# ISOW7844DWE.net
KiCad netlist of a schematic drawn in Altium Designer
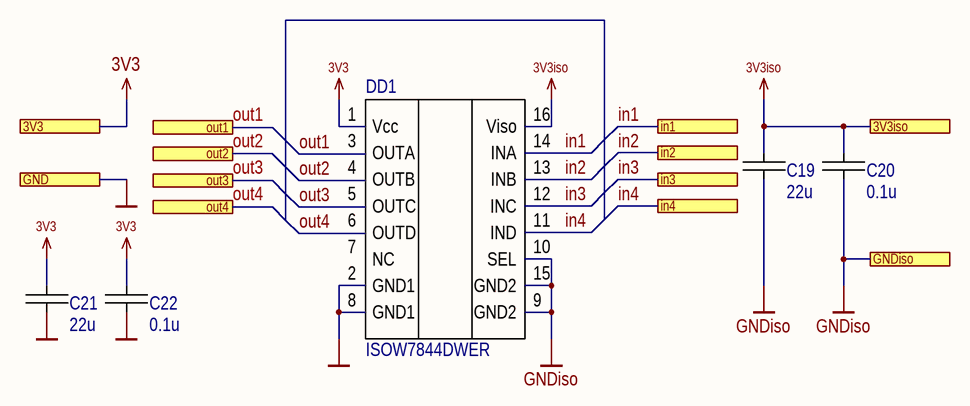
[diagram p0: ISOW7844DWE.SchDoc]

(export (version "E")
  (design (tool "Eeschema 10.0.6"))
  (components
    (comp (ref "C19")
      (value "22u")
      (footprint "C0805_IPC")
      (description "22µF ±20% 6.3V Ceramic Capacitor X5R 0805 (2012 Metric)")
      (fields (field (name "MPN") "CL21A226MQQNNNE") (field (name "TOLERANCE") "0.2"))
      (libsource (lib "DB_res_cap_ind") (part "C0805_GOST"))
    )
    (comp (ref "C20")
      (value "0.1u")
      (footprint "C0603_IPC")
      (description "0.1uF ±10% 50V Ceramic Capacitor X7R 0603 (1608 Metric)")
      (fields (field (name "MPN") "CL10B104KB8NNND") (field (name "TOLERANCE") "0,1"))
      (libsource (lib "DB_res_cap_ind") (part "C0603_GOST"))
    )
    (comp (ref "C21")
      (value "22u")
      (footprint "C0805_IPC")
      (description "22µF ±20% 6.3V Ceramic Capacitor X5R 0805 (2012 Metric)")
      (fields (field (name "MPN") "CL21A226MQQNNNE") (field (name "TOLERANCE") "0.2"))
      (libsource (lib "DB_res_cap_ind") (part "C0805_GOST"))
    )
    (comp (ref "C22")
      (value "0.1u")
      (footprint "C0603_IPC")
      (description "0.1uF ±10% 50V Ceramic Capacitor X7R 0603 (1608 Metric)")
      (fields (field (name "MPN") "CL10B104KB8NNND") (field (name "TOLERANCE") "0,1"))
      (libsource (lib "DB_res_cap_ind") (part "C0603_GOST"))
    )
    (comp (ref "DD1")
      (value "ISOW7844DWER")
      (footprint "SOIC16W")
      (fields (field (name "MANUFACTURER") "Texas Instruments"))
      (libsource (lib "DB_IC") (part "ISOW7844DWER"))
    )
  )
  (nets
    (net (code "2") (name "/in1") (class "Default")
      (node (ref "DD1") (pin "14") (pinfunction "INA_14") (pintype "passive"))
    )
    (net (code "3") (name "/in2") (class "Default")
      (node (ref "DD1") (pin "13") (pinfunction "INB_13") (pintype "passive"))
    )
    (net (code "4") (name "/in3") (class "Default")
      (node (ref "DD1") (pin "12") (pinfunction "INC_12") (pintype "passive"))
    )
    (net (code "5") (name "/in4") (class "Default")
      (node (ref "DD1") (pin "11") (pinfunction "IND_11") (pintype "passive"))
    )
    (net (code "6") (name "3V3") (class "Default")
      (node (ref "C21") (pin "1") (pinfunction "1_1") (pintype "passive"))
      (node (ref "C22") (pin "1") (pinfunction "1_1") (pintype "passive"))
      (node (ref "DD1") (pin "1") (pinfunction "Vcc_1") (pintype "passive"))
    )
    (net (code "7") (name "3V3iso") (class "Default")
      (node (ref "C19") (pin "1") (pinfunction "1_1") (pintype "passive"))
      (node (ref "C20") (pin "1") (pinfunction "1_1") (pintype "passive"))
      (node (ref "DD1") (pin "16") (pinfunction "Viso_16") (pintype "passive"))
    )
    (net (code "8") (name "GND") (class "Default")
      (node (ref "C21") (pin "2") (pinfunction "2_2") (pintype "passive"))
      (node (ref "C22") (pin "2") (pinfunction "2_2") (pintype "passive"))
      (node (ref "DD1") (pin "2") (pinfunction "GND1_2") (pintype "passive"))
      (node (ref "DD1") (pin "8") (pinfunction "GND1_8") (pintype "passive"))
    )
    (net (code "9") (name "GNDiso") (class "Default")
      (node (ref "C19") (pin "2") (pinfunction "2_2") (pintype "passive"))
      (node (ref "C20") (pin "2") (pinfunction "2_2") (pintype "passive"))
      (node (ref "DD1") (pin "10") (pinfunction "SEL_10") (pintype "passive"))
      (node (ref "DD1") (pin "15") (pinfunction "GND2_15") (pintype "passive"))
      (node (ref "DD1") (pin "9") (pinfunction "GND2_9") (pintype "passive"))
    )
    (net (code "10") (name "unconnected-(DD1-NC-Pad1)") (class "Default")
      (node (ref "DD1") (pin "1") (pinfunction "NC_1") (pintype "passive"))
    )
    (net (code "11") (name "unconnected-(DD1-NC-Pad2)") (class "Default")
      (node (ref "DD1") (pin "2") (pinfunction "NC_2") (pintype "tri_state"))
    )
    (net (code "12") (name "unconnected-(DD1-NC-Pad7)") (class "Default")
      (node (ref "DD1") (pin "7") (pinfunction "NC_7") (pintype "passive"))
    )
    (net (code "13") (name "unconnected-(DD1-OUTA-Pad3)") (class "Default")
      (node (ref "DD1") (pin "3") (pinfunction "OUTA_3") (pintype "passive"))
    )
    (net (code "14") (name "unconnected-(DD1-OUTB-Pad4)") (class "Default")
      (node (ref "DD1") (pin "4") (pinfunction "OUTB_4") (pintype "passive"))
    )
    (net (code "15") (name "unconnected-(DD1-OUTC-Pad5)") (class "Default")
      (node (ref "DD1") (pin "5") (pinfunction "OUTC_5") (pintype "passive"))
    )
    (net (code "16") (name "unconnected-(DD1-OUTD-Pad6)") (class "Default")
      (node (ref "DD1") (pin "6") (pinfunction "OUTD_6") (pintype "passive"))
    )
  )
)
